# MCU_LCD.net
KiCad netlist of a schematic drawn in Altium Designer
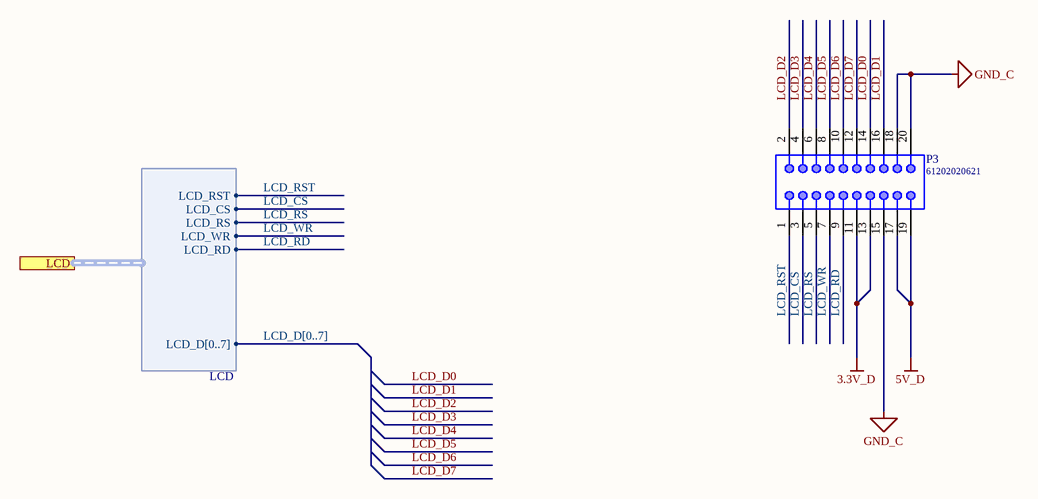
[diagram p0: MCU_LCD.SchDoc]

(export (version "E")
  (design (tool "Eeschema 10.0.6"))
  (components
    (comp (ref "P3")
      (value "61202020621")
      (footprint "61202020621")
      (description "Male Box Header WR-BHD, SMT, Vertical, pitch 2.54 mm, 20 pins")
      (fields (field (name "PUBLISHER") "Wurth Elektronik"))
      (libsource (lib "o162711v243 Altium_WR-BHD (rev19a)") (part "61202020621"))
    )
  )
  (nets
    (net (code "2") (name "/LCD_CS") (class "Default")
      (node (ref "P3") (pin "3") (pinfunction "3_3") (pintype "passive"))
    )
    (net (code "3") (name "/LCD_D0") (class "Default")
      (node (ref "P3") (pin "14") (pinfunction "14_14") (pintype "passive"))
    )
    (net (code "4") (name "/LCD_D1") (class "Default")
      (node (ref "P3") (pin "16") (pinfunction "16_16") (pintype "passive"))
    )
    (net (code "5") (name "/LCD_D2") (class "Default")
      (node (ref "P3") (pin "2") (pinfunction "2_2") (pintype "passive"))
    )
    (net (code "6") (name "/LCD_D3") (class "Default")
      (node (ref "P3") (pin "4") (pinfunction "4_4") (pintype "passive"))
    )
    (net (code "7") (name "/LCD_D4") (class "Default")
      (node (ref "P3") (pin "6") (pinfunction "6_6") (pintype "passive"))
    )
    (net (code "8") (name "/LCD_D5") (class "Default")
      (node (ref "P3") (pin "8") (pinfunction "8_8") (pintype "passive"))
    )
    (net (code "9") (name "/LCD_D6") (class "Default")
      (node (ref "P3") (pin "10") (pinfunction "10_10") (pintype "passive"))
    )
    (net (code "10") (name "/LCD_D7") (class "Default")
      (node (ref "P3") (pin "12") (pinfunction "12_12") (pintype "passive"))
    )
    (net (code "11") (name "/LCD_RD") (class "Default")
      (node (ref "P3") (pin "9") (pinfunction "9_9") (pintype "passive"))
    )
    (net (code "12") (name "/LCD_RS") (class "Default")
      (node (ref "P3") (pin "5") (pinfunction "5_5") (pintype "passive"))
    )
    (net (code "13") (name "/LCD_RST") (class "Default")
      (node (ref "P3") (pin "1") (pinfunction "1_1") (pintype "passive"))
    )
    (net (code "14") (name "/LCD_WR") (class "Default")
      (node (ref "P3") (pin "7") (pinfunction "7_7") (pintype "passive"))
    )
    (net (code "17") (name "3.3V_D") (class "Default")
      (node (ref "P3") (pin "11") (pinfunction "11_11") (pintype "passive"))
      (node (ref "P3") (pin "13") (pinfunction "13_13") (pintype "passive"))
    )
    (net (code "18") (name "5V_D") (class "Default")
      (node (ref "P3") (pin "17") (pinfunction "17_17") (pintype "passive"))
      (node (ref "P3") (pin "19") (pinfunction "19_19") (pintype "passive"))
    )
    (net (code "19") (name "GND_C") (class "Default")
      (node (ref "P3") (pin "15") (pinfunction "15_15") (pintype "passive"))
      (node (ref "P3") (pin "18") (pinfunction "18_18") (pintype "passive"))
      (node (ref "P3") (pin "20") (pinfunction "20_20") (pintype "passive"))
    )
  )
)
